# PX4FMUv2_4_6_07.net
KiCad netlist of a schematic drawn in Altium Designer
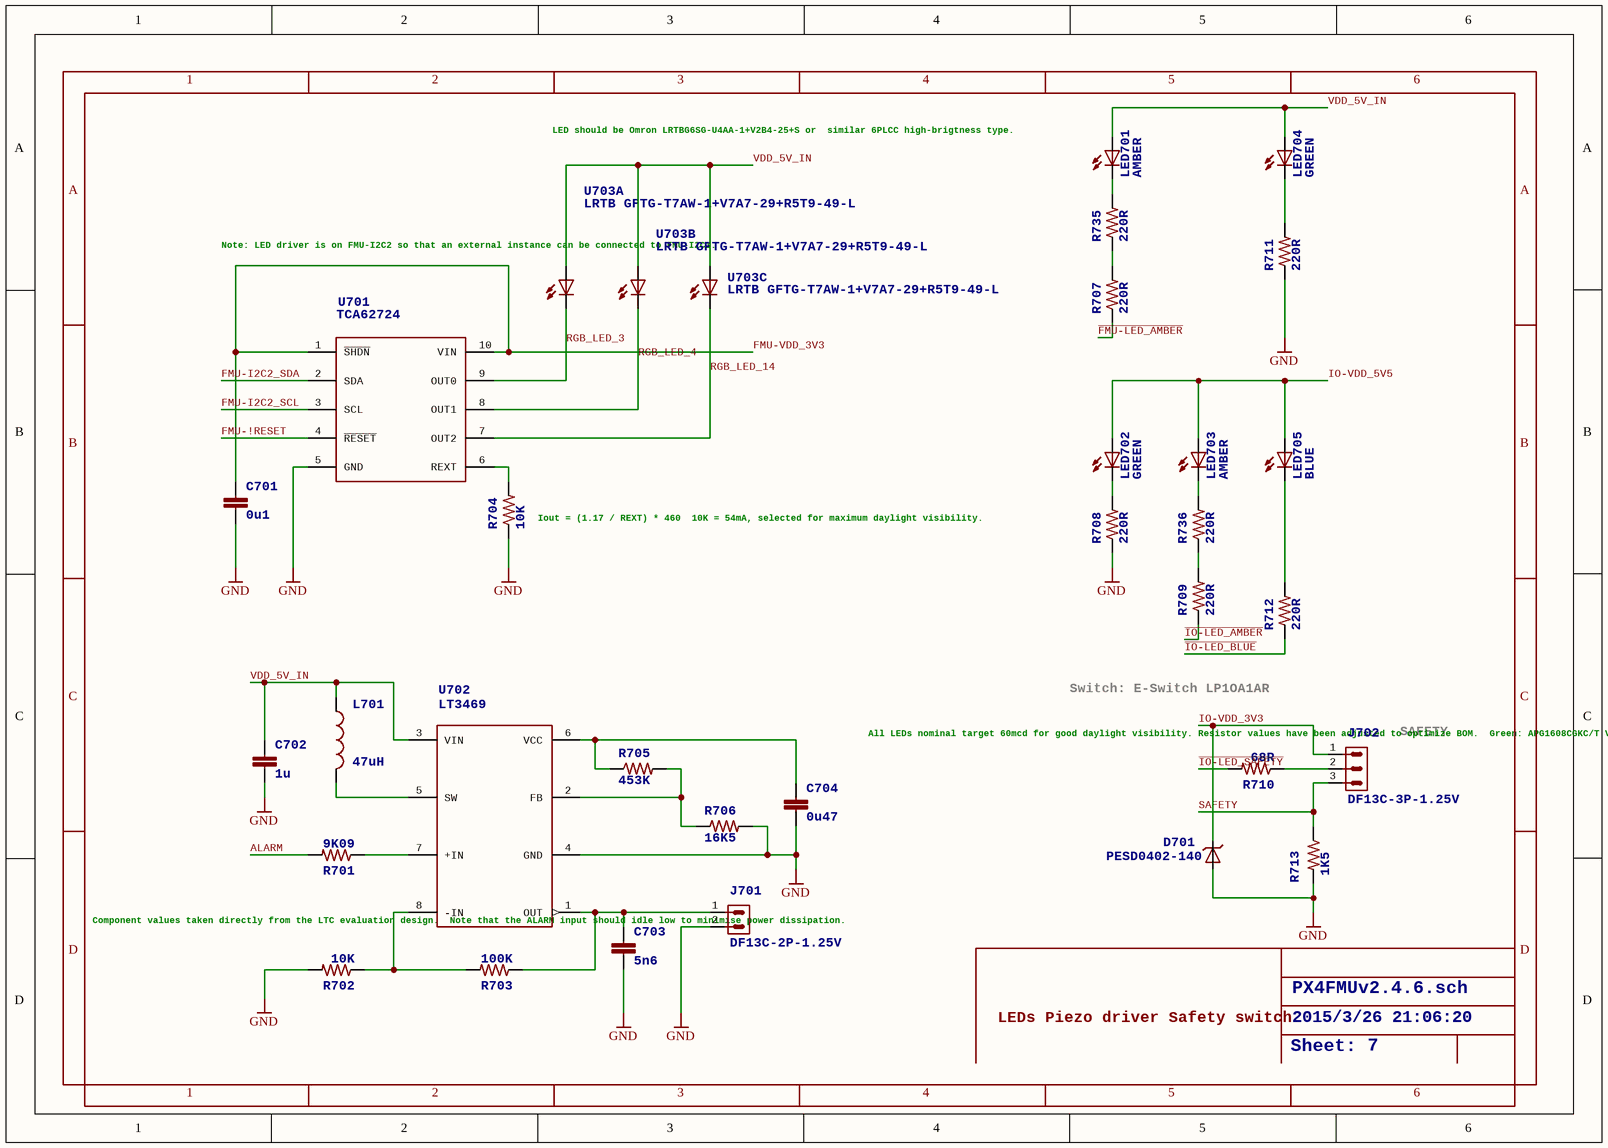
[diagram p0: PX4FMUv2.4.6_07.SchDoc]

(export (version "E")
  (design (tool "Eeschema 10.0.6"))
  (components
    (comp (ref "C701")
      (value "0u1")
      (footprint "0402-CAP")
      (description "<b>Capacitor</b>\nStandard 0603 ceramic capacitor, and 0.1\" leaded capacitor.")
      (fields (field (name "PARTNO") "CC0402ZRY5V7BB104"))
      (libsource (lib "pixhawk2") (part "CAP0402"))
    )
    (comp (ref "C702")
      (value "1u")
      (footprint "0603-CAP")
      (description "<b>Capacitor</b>\nStandard 0603 ceramic capacitor, and 0.1\" leaded capacitor.")
      (fields (field (name "PARTNO") "CC0603ZRY5V7BB105"))
      (libsource (lib "pixhawk2") (part "CAP0603"))
    )
    (comp (ref "C703")
      (value "5n6")
      (footprint "0402-CAP")
      (description "<b>Capacitor</b>\nStandard 0603 ceramic capacitor, and 0.1\" leaded capacitor.")
      (fields (field (name "PARTNO") "C0402C562K5RACTU"))
      (libsource (lib "pixhawk2") (part "CAP0402"))
    )
    (comp (ref "C704")
      (value "0u47")
      (footprint "0402-CAP")
      (description "<b>Capacitor</b>\nStandard 0603 ceramic capacitor, and 0.1\" leaded capacitor.")
      (fields (field (name "PARTNO") "C1005X5R1C474K050BC"))
      (libsource (lib "pixhawk2") (part "CAP0402"))
    )
    (comp (ref "D701")
      (value "PESD0402-140")
      (footprint "0402-TVS")
      (libsource (lib "pixhawk2") (part "DIODE-TVS"))
    )
    (comp (ref "J701")
      (value "DF13C-2P-1.25V")
      (footprint "DF13C-2P-1.25V")
      (description "DF13-2P\n1.25mm Pitch Miniature Crimping Connector.")
      (fields (field (name "PARTNO") "DF13C-2P-1.25V(20)"))
      (libsource (lib "con-hirose-df13") (part "DF13-2P-1.25V"))
    )
    (comp (ref "J702")
      (value "DF13C-3P-1.25V")
      (footprint "DF13C-3P-1.25V")
      (description "DF13-3P\n1.25mm Pitch Miniature Crimping Connector.")
      (fields (field (name "PARTNO") "DF13C-3P-1.25V(20)"))
      (libsource (lib "con-hirose-df13") (part "DF13-3P-1.25V"))
    )
    (comp (ref "L701")
      (value "47uH")
      (footprint "0805-IND")
      (fields (field (name "PARTNO") "MLZ2012M470W"))
      (libsource (lib "pixhawk2") (part "INDUCTOR0805"))
    )
    (comp (ref "LED701")
      (value "AMBER")
      (footprint "0603-LED")
      (fields (field (name "PARTNO") "APTD1608SECK"))
      (libsource (lib "pixhawk2") (part "LED0603"))
    )
    (comp (ref "LED702")
      (value "GREEN")
      (footprint "0603-LED")
      (fields (field (name "PARTNO") "APTD1608CGCK"))
      (libsource (lib "pixhawk2") (part "LED0603"))
    )
    (comp (ref "LED703")
      (value "AMBER")
      (footprint "0603-LED")
      (fields (field (name "PARTNO") "APTD1608SECK"))
      (libsource (lib "pixhawk2") (part "LED0603"))
    )
    (comp (ref "LED704")
      (value "GREEN")
      (footprint "0603-LED")
      (fields (field (name "PARTNO") "APTD1608CGCK"))
      (libsource (lib "pixhawk2") (part "LED0603"))
    )
    (comp (ref "LED705")
      (value "BLUE")
      (footprint "0603-LED")
      (fields (field (name "PARTNO") "APTD1608QBC/D"))
      (libsource (lib "pixhawk2") (part "LED0603"))
    )
    (comp (ref "R701")
      (value "9K09")
      (footprint "0402-RES")
      (fields (field (name "PARTNO") "RMCF0402FT9K09"))
      (libsource (lib "pixhawk2") (part "RESISTOR0402-RES"))
    )
    (comp (ref "R702")
      (value "10K")
      (footprint "0402-RES")
      (fields (field (name "PARTNO") "RC0402FR-0710KL"))
      (libsource (lib "pixhawk2") (part "RESISTOR0402-RES"))
    )
    (comp (ref "R703")
      (value "100K")
      (footprint "0402-RES")
      (fields (field (name "PARTNO") "RC0402FR-07100KL"))
      (libsource (lib "pixhawk2") (part "RESISTOR0402-RES"))
    )
    (comp (ref "R704")
      (value "10K")
      (footprint "0402-RES")
      (fields (field (name "PARTNO") "RC0402FR-0710KL"))
      (libsource (lib "pixhawk2") (part "RESISTOR0402-RES"))
    )
    (comp (ref "R705")
      (value "453K")
      (footprint "0402-RES")
      (fields (field (name "PARTNO") "RMCF0402FT453K"))
      (libsource (lib "pixhawk2") (part "RESISTOR0402-RES"))
    )
    (comp (ref "R706")
      (value "16K5")
      (footprint "0402-RES")
      (fields (field (name "PARTNO") "RMCF0402FT16K5"))
      (libsource (lib "pixhawk2") (part "RESISTOR0402-RES"))
    )
    (comp (ref "R707")
      (value "220R")
      (footprint "0402-RES")
      (fields (field (name "PARTNO") "RC0402FR-07220RL"))
      (libsource (lib "pixhawk2") (part "RESISTOR0402-RES"))
    )
    (comp (ref "R708")
      (value "220R")
      (footprint "0402-RES")
      (fields (field (name "PARTNO") "RC0402FR-07220RL"))
      (libsource (lib "pixhawk2") (part "RESISTOR0402-RES"))
    )
    (comp (ref "R709")
      (value "220R")
      (footprint "0402-RES")
      (fields (field (name "PARTNO") "RC0402FR-07220RL"))
      (libsource (lib "pixhawk2") (part "RESISTOR0402-RES"))
    )
    (comp (ref "R710")
      (value "68R")
      (footprint "0402-RES")
      (fields (field (name "PARTNO") "ERJ-2GEJ680X"))
      (libsource (lib "pixhawk2") (part "RESISTOR0402-RES"))
    )
    (comp (ref "R711")
      (value "220R")
      (footprint "0402-RES")
      (fields (field (name "PARTNO") "RC0402FR-07220RL"))
      (libsource (lib "pixhawk2") (part "RESISTOR0402-RES"))
    )
    (comp (ref "R712")
      (value "220R")
      (footprint "0402-RES")
      (fields (field (name "PARTNO") "RC0402FR-07220RL"))
      (libsource (lib "pixhawk2") (part "RESISTOR0402-RES"))
    )
    (comp (ref "R713")
      (value "1K5")
      (footprint "0402-RES")
      (libsource (lib "pixhawk2") (part "RESISTOR0402-RES"))
    )
    (comp (ref "R735")
      (value "220R")
      (footprint "0402-RES")
      (fields (field (name "PARTNO") "RC0402FR-07220RL"))
      (libsource (lib "pixhawk2") (part "RESISTOR0402-RES"))
    )
    (comp (ref "R736")
      (value "220R")
      (footprint "0402-RES")
      (fields (field (name "PARTNO") "RC0402FR-07220RL"))
      (libsource (lib "pixhawk2") (part "RESISTOR0402-RES"))
    )
    (comp (ref "U701")
      (value "TCA62724FMG")
      (footprint "SON10")
      (description "Toshiba TCA62724FMG I2C RGB LED driver")
      (fields (field (name "TCA62724") "TCA62724"))
      (libsource (lib "pixhawk2") (part "TCA62724FMG"))
    )
    (comp (ref "U702")
      (value "LT3469")
      (footprint "SOT23-8")
      (description "LT3469 Piezo microactuator driver with boost regulator")
      (fields (field (name "PARTNO") "LT3469ETS8"))
      (libsource (lib "pixhawk2") (part "LT3469"))
    )
    (comp (ref "U703")
      (value "LRTB GFTG-T7AW-1+V7A7-29+R5T9-49-L")
      (footprint "6-PLCC")
      (description "RGB LED with separate anode/cathode terminals")
      (libsource (lib "pixhawk2") (part "RGB-LED6-PLCC"))
    )
  )
  (nets
    (net (code "1") (name "/ALARM") (class "Default")
      (node (ref "R701") (pin "P$2") (pinfunction "2_P$2") (pintype "passive"))
    )
    (net (code "2") (name "/FMU-!RESET") (class "Default")
      (node (ref "U701") (pin "4") (pinfunction "~{RESET}_4") (pintype "passive"))
    )
    (net (code "3") (name "/FMU-I2C2_SCL") (class "Default")
      (node (ref "U701") (pin "3") (pinfunction "SCL_3") (pintype "passive"))
    )
    (net (code "4") (name "/FMU-I2C2_SDA") (class "Default")
      (node (ref "U701") (pin "2") (pinfunction "SDA_2") (pintype "passive"))
    )
    (net (code "5") (name "/FMU-VDD_3V3") (class "Default")
      (node (ref "C701") (pin "P$1") (pinfunction "1_P$1") (pintype "passive"))
      (node (ref "U701") (pin "1") (pinfunction "~{SHDN}_1") (pintype "passive"))
      (node (ref "U701") (pin "10") (pinfunction "VIN_10") (pintype "power_in"))
    )
    (net (code "6") (name "/IO-VDD_3V3") (class "Default")
      (node (ref "D701") (pin "C") (pinfunction "C_C") (pintype "passive"))
      (node (ref "J702") (pin "1") (pinfunction "1_1") (pintype "passive"))
    )
    (net (code "7") (name "/IO-VDD_5V5") (class "Default")
      (node (ref "LED702") (pin "A") (pinfunction "A_A") (pintype "passive"))
      (node (ref "LED703") (pin "A") (pinfunction "A_A") (pintype "passive"))
      (node (ref "LED705") (pin "A") (pinfunction "A_A") (pintype "passive"))
    )
    (net (code "8") (name "/RGB_LED_3") (class "Default")
      (node (ref "U701") (pin "9") (pinfunction "OUT0_9") (pintype "open_collector"))
      (node (ref "U703") (pin "C1") (pinfunction "C_C1") (pintype "passive"))
    )
    (net (code "9") (name "/RGB_LED_4") (class "Default")
      (node (ref "U701") (pin "8") (pinfunction "OUT1_8") (pintype "open_collector"))
      (node (ref "U703") (pin "C2") (pinfunction "C_C2") (pintype "passive"))
    )
    (net (code "10") (name "/RGB_LED_14") (class "Default")
      (node (ref "U701") (pin "7") (pinfunction "OUT2_7") (pintype "open_collector"))
      (node (ref "U703") (pin "C3") (pinfunction "C_C3") (pintype "passive"))
    )
    (net (code "11") (name "/SAFETY") (class "Default")
      (node (ref "J702") (pin "3") (pinfunction "3_3") (pintype "passive"))
      (node (ref "R713") (pin "P$1") (pinfunction "1_P$1") (pintype "passive"))
    )
    (net (code "12") (name "/VDD_5V_IN") (class "Default")
      (node (ref "C702") (pin "P$1") (pinfunction "1_P$1") (pintype "passive"))
      (node (ref "L701") (pin "P$1") (pinfunction "1_P$1") (pintype "passive"))
      (node (ref "LED701") (pin "A") (pinfunction "A_A") (pintype "passive"))
      (node (ref "LED704") (pin "A") (pinfunction "A_A") (pintype "passive"))
      (node (ref "U702") (pin "3") (pinfunction "VIN_3") (pintype "power_in"))
      (node (ref "U703") (pin "A1") (pinfunction "A_A1") (pintype "passive"))
      (node (ref "U703") (pin "A2") (pinfunction "A_A2") (pintype "passive"))
      (node (ref "U703") (pin "A3") (pinfunction "A_A3") (pintype "passive"))
    )
    (net (code "13") (name "/~{FMU-LED_AMBER}") (class "Default")
      (node (ref "R707") (pin "P$1") (pinfunction "1_P$1") (pintype "passive"))
    )
    (net (code "14") (name "/~{IO-LED_AMBER}") (class "Default")
      (node (ref "R709") (pin "P$1") (pinfunction "1_P$1") (pintype "passive"))
    )
    (net (code "15") (name "/~{IO-LED_BLUE}") (class "Default")
      (node (ref "R712") (pin "P$1") (pinfunction "1_P$1") (pintype "passive"))
    )
    (net (code "16") (name "/~{IO-LED_SAFETY}") (class "Default")
      (node (ref "R710") (pin "P$2") (pinfunction "2_P$2") (pintype "passive"))
    )
    (net (code "17") (name "GND") (class "Default")
      (node (ref "C701") (pin "P$2") (pinfunction "2_P$2") (pintype "passive"))
      (node (ref "C702") (pin "P$2") (pinfunction "2_P$2") (pintype "passive"))
      (node (ref "C703") (pin "P$2") (pinfunction "2_P$2") (pintype "passive"))
      (node (ref "C704") (pin "P$2") (pinfunction "2_P$2") (pintype "passive"))
      (node (ref "D701") (pin "A") (pinfunction "A_A") (pintype "passive"))
      (node (ref "J701") (pin "2") (pinfunction "2_2") (pintype "passive"))
      (node (ref "R702") (pin "P$2") (pinfunction "2_P$2") (pintype "passive"))
      (node (ref "R704") (pin "P$1") (pinfunction "1_P$1") (pintype "passive"))
      (node (ref "R706") (pin "P$2") (pinfunction "2_P$2") (pintype "passive"))
      (node (ref "R708") (pin "P$1") (pinfunction "1_P$1") (pintype "passive"))
      (node (ref "R711") (pin "P$1") (pinfunction "1_P$1") (pintype "passive"))
      (node (ref "R713") (pin "P$2") (pinfunction "2_P$2") (pintype "passive"))
      (node (ref "U701") (pin "5") (pinfunction "GND_5") (pintype "power_in"))
      (node (ref "U702") (pin "4") (pinfunction "GND_4") (pintype "power_in"))
    )
    (net (code "18") (name "Net-(C703-1)") (class "Default")
      (node (ref "C703") (pin "P$1") (pinfunction "1_P$1") (pintype "passive"))
      (node (ref "J701") (pin "1") (pinfunction "1_1") (pintype "passive"))
      (node (ref "R703") (pin "P$1") (pinfunction "1_P$1") (pintype "passive"))
      (node (ref "U702") (pin "1") (pinfunction "OUT_1") (pintype "output"))
    )
    (net (code "19") (name "Net-(C704-1)") (class "Default")
      (node (ref "C704") (pin "P$1") (pinfunction "1_P$1") (pintype "passive"))
      (node (ref "R705") (pin "P$1") (pinfunction "1_P$1") (pintype "passive"))
      (node (ref "U702") (pin "6") (pinfunction "VCC_6") (pintype "passive"))
    )
    (net (code "20") (name "Net-(L701-2)") (class "Default")
      (node (ref "L701") (pin "P$2") (pinfunction "2_P$2") (pintype "passive"))
      (node (ref "U702") (pin "5") (pinfunction "SW_5") (pintype "passive"))
    )
    (net (code "21") (name "Net-(R701-1)") (class "Default")
      (node (ref "R701") (pin "P$1") (pinfunction "1_P$1") (pintype "passive"))
      (node (ref "U702") (pin "7") (pinfunction "+IN_7") (pintype "passive"))
    )
    (net (code "22") (name "Net-(R702-1)") (class "Default")
      (node (ref "R702") (pin "P$1") (pinfunction "1_P$1") (pintype "passive"))
      (node (ref "R703") (pin "P$2") (pinfunction "2_P$2") (pintype "passive"))
      (node (ref "U702") (pin "8") (pinfunction "-IN_8") (pintype "passive"))
    )
    (net (code "23") (name "Net-(R704-2)") (class "Default")
      (node (ref "R704") (pin "P$2") (pinfunction "2_P$2") (pintype "passive"))
      (node (ref "U701") (pin "6") (pinfunction "REXT_6") (pintype "passive"))
    )
    (net (code "24") (name "Net-(R705-2)") (class "Default")
      (node (ref "R705") (pin "P$2") (pinfunction "2_P$2") (pintype "passive"))
      (node (ref "R706") (pin "P$1") (pinfunction "1_P$1") (pintype "passive"))
      (node (ref "U702") (pin "2") (pinfunction "FB_2") (pintype "passive"))
    )
    (net (code "25") (name "Net-(R707-2)") (class "Default")
      (node (ref "R707") (pin "P$2") (pinfunction "2_P$2") (pintype "passive"))
      (node (ref "R735") (pin "P$1") (pinfunction "1_P$1") (pintype "passive"))
    )
    (net (code "26") (name "Net-(R708-2)") (class "Default")
      (node (ref "LED702") (pin "C") (pinfunction "C_C") (pintype "passive"))
      (node (ref "R708") (pin "P$2") (pinfunction "2_P$2") (pintype "passive"))
    )
    (net (code "27") (name "Net-(R709-2)") (class "Default")
      (node (ref "R709") (pin "P$2") (pinfunction "2_P$2") (pintype "passive"))
      (node (ref "R736") (pin "P$1") (pinfunction "1_P$1") (pintype "passive"))
    )
    (net (code "28") (name "Net-(R710-1)") (class "Default")
      (node (ref "J702") (pin "2") (pinfunction "2_2") (pintype "passive"))
      (node (ref "R710") (pin "P$1") (pinfunction "1_P$1") (pintype "passive"))
    )
    (net (code "29") (name "Net-(R711-2)") (class "Default")
      (node (ref "LED704") (pin "C") (pinfunction "C_C") (pintype "passive"))
      (node (ref "R711") (pin "P$2") (pinfunction "2_P$2") (pintype "passive"))
    )
    (net (code "30") (name "Net-(R712-2)") (class "Default")
      (node (ref "LED705") (pin "C") (pinfunction "C_C") (pintype "passive"))
      (node (ref "R712") (pin "P$2") (pinfunction "2_P$2") (pintype "passive"))
    )
    (net (code "31") (name "Net-(R735-2)") (class "Default")
      (node (ref "LED701") (pin "C") (pinfunction "C_C") (pintype "passive"))
      (node (ref "R735") (pin "P$2") (pinfunction "2_P$2") (pintype "passive"))
    )
    (net (code "32") (name "Net-(R736-2)") (class "Default")
      (node (ref "LED703") (pin "C") (pinfunction "C_C") (pintype "passive"))
      (node (ref "R736") (pin "P$2") (pinfunction "2_P$2") (pintype "passive"))
    )
  )
)
